# km11.net
KiCad netlist of a schematic drawn in EAGLE
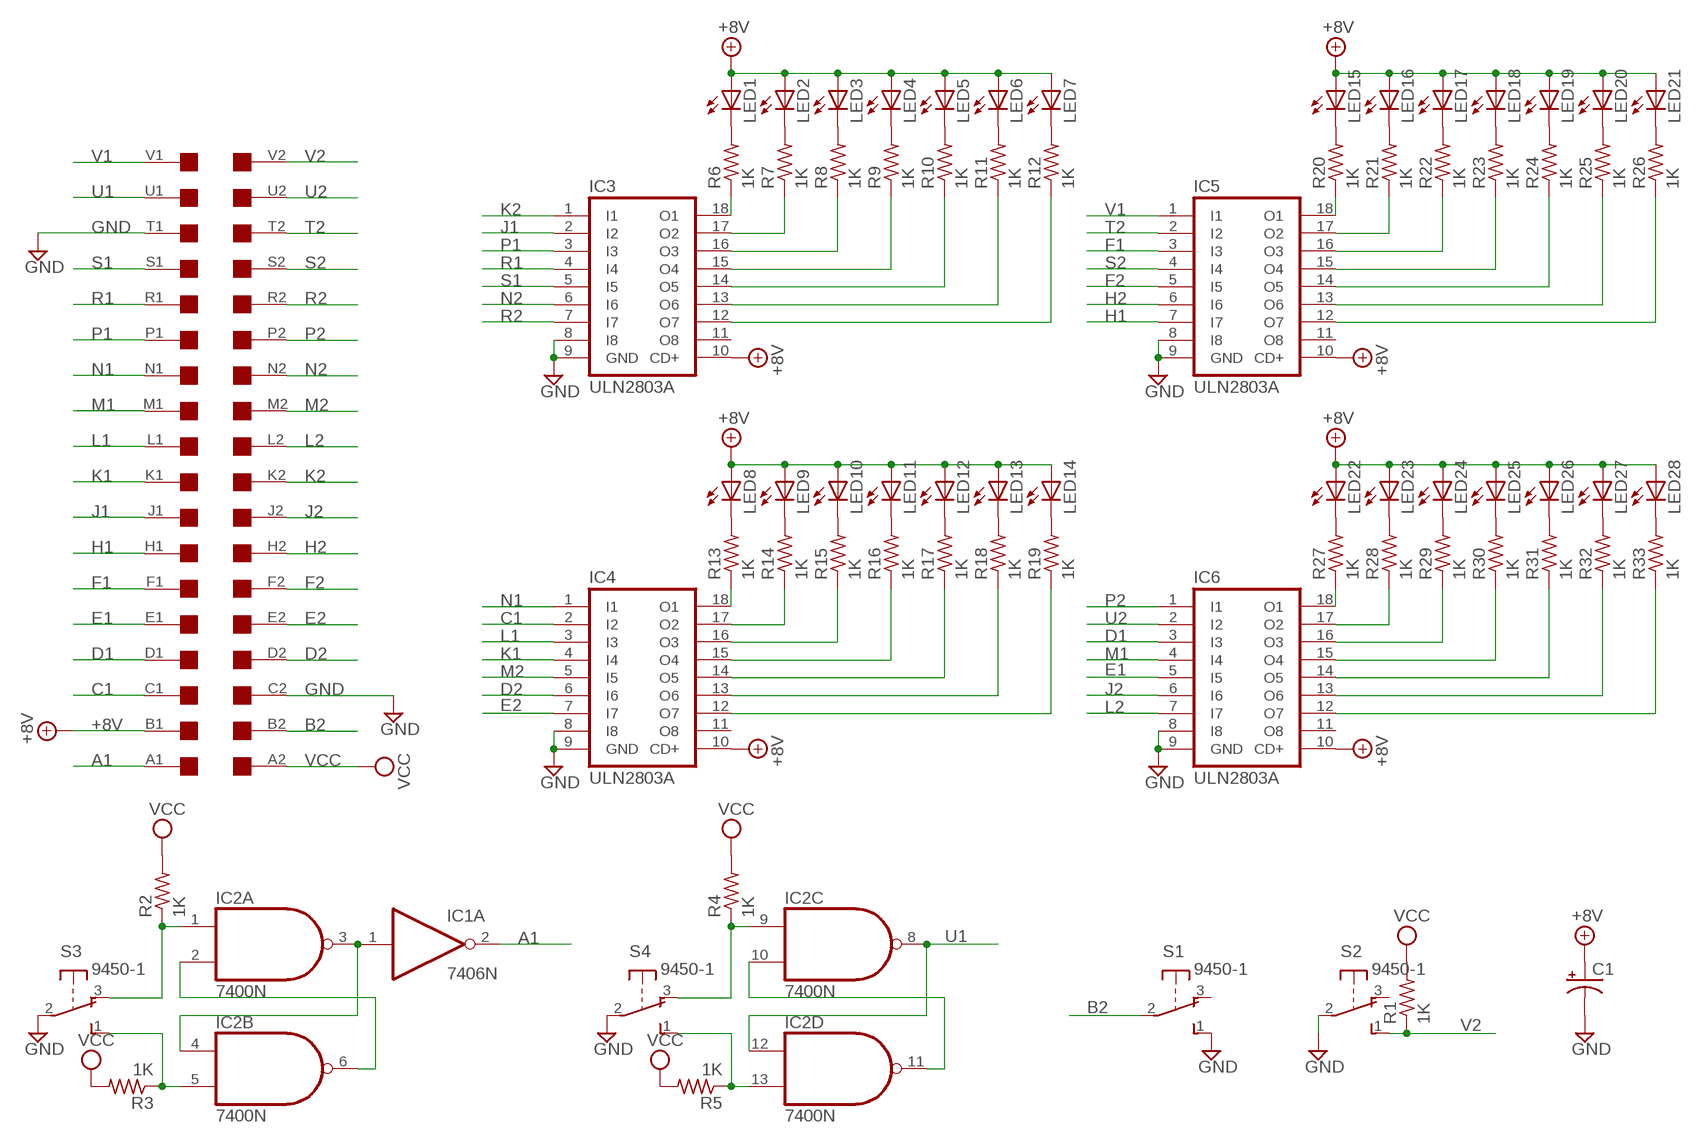
[diagram p0: schematic, sheet 1]

(export (version "E")
  (design (tool "Eeschema 10.0.6"))
  (components
    (comp (ref "C1")
      (value "CPOL-USE22-6AXIAL")
      (footprint "eagle-import:E22-6")
      (libsource (lib "eagle-import") (part "CPOL-USE22-6AXIAL"))
    )
    (comp (ref "IC1")
      (value "7406N")
      (footprint "eagle-import:DIL14")
      (libsource (lib "eagle-import") (part "7406N"))
    )
    (comp (ref "IC2")
      (value "7400N")
      (footprint "eagle-import:DIL14")
      (libsource (lib "eagle-import") (part "7400N"))
    )
    (comp (ref "IC3")
      (value "ULN2803A")
      (footprint "eagle-import:DIL18")
      (libsource (lib "eagle-import") (part "ULN2803A"))
    )
    (comp (ref "IC4")
      (value "ULN2803A")
      (footprint "eagle-import:DIL18")
      (libsource (lib "eagle-import") (part "ULN2803A"))
    )
    (comp (ref "IC5")
      (value "ULN2803A")
      (footprint "eagle-import:DIL18")
      (libsource (lib "eagle-import") (part "ULN2803A"))
    )
    (comp (ref "IC6")
      (value "ULN2803A")
      (footprint "eagle-import:DIL18")
      (libsource (lib "eagle-import") (part "ULN2803A"))
    )
    (comp (ref "LED1")
      (value "LED3MM")
      (footprint "eagle-import:LED3MM")
      (libsource (lib "eagle-import") (part "LED3MM"))
    )
    (comp (ref "LED2")
      (value "LED3MM")
      (footprint "eagle-import:LED3MM")
      (libsource (lib "eagle-import") (part "LED3MM"))
    )
    (comp (ref "LED3")
      (value "LED3MM")
      (footprint "eagle-import:LED3MM")
      (libsource (lib "eagle-import") (part "LED3MM"))
    )
    (comp (ref "LED4")
      (value "LED3MM")
      (footprint "eagle-import:LED3MM")
      (libsource (lib "eagle-import") (part "LED3MM"))
    )
    (comp (ref "LED5")
      (value "LED3MM")
      (footprint "eagle-import:LED3MM")
      (libsource (lib "eagle-import") (part "LED3MM"))
    )
    (comp (ref "LED6")
      (value "LED3MM")
      (footprint "eagle-import:LED3MM")
      (libsource (lib "eagle-import") (part "LED3MM"))
    )
    (comp (ref "LED7")
      (value "LED3MM")
      (footprint "eagle-import:LED3MM")
      (libsource (lib "eagle-import") (part "LED3MM"))
    )
    (comp (ref "LED8")
      (value "LED3MM")
      (footprint "eagle-import:LED3MM")
      (libsource (lib "eagle-import") (part "LED3MM"))
    )
    (comp (ref "LED9")
      (value "LED3MM")
      (footprint "eagle-import:LED3MM")
      (libsource (lib "eagle-import") (part "LED3MM"))
    )
    (comp (ref "LED10")
      (value "LED3MM")
      (footprint "eagle-import:LED3MM")
      (libsource (lib "eagle-import") (part "LED3MM"))
    )
    (comp (ref "LED11")
      (value "LED3MM")
      (footprint "eagle-import:LED3MM")
      (libsource (lib "eagle-import") (part "LED3MM"))
    )
    (comp (ref "LED12")
      (value "LED3MM")
      (footprint "eagle-import:LED3MM")
      (libsource (lib "eagle-import") (part "LED3MM"))
    )
    (comp (ref "LED13")
      (value "LED3MM")
      (footprint "eagle-import:LED3MM")
      (libsource (lib "eagle-import") (part "LED3MM"))
    )
    (comp (ref "LED14")
      (value "LED3MM")
      (footprint "eagle-import:LED3MM")
      (libsource (lib "eagle-import") (part "LED3MM"))
    )
    (comp (ref "LED15")
      (value "LED3MM")
      (footprint "eagle-import:LED3MM")
      (libsource (lib "eagle-import") (part "LED3MM"))
    )
    (comp (ref "LED16")
      (value "LED3MM")
      (footprint "eagle-import:LED3MM")
      (libsource (lib "eagle-import") (part "LED3MM"))
    )
    (comp (ref "LED17")
      (value "LED3MM")
      (footprint "eagle-import:LED3MM")
      (libsource (lib "eagle-import") (part "LED3MM"))
    )
    (comp (ref "LED18")
      (value "LED3MM")
      (footprint "eagle-import:LED3MM")
      (libsource (lib "eagle-import") (part "LED3MM"))
    )
    (comp (ref "LED19")
      (value "LED3MM")
      (footprint "eagle-import:LED3MM")
      (libsource (lib "eagle-import") (part "LED3MM"))
    )
    (comp (ref "LED20")
      (value "LED3MM")
      (footprint "eagle-import:LED3MM")
      (libsource (lib "eagle-import") (part "LED3MM"))
    )
    (comp (ref "LED21")
      (value "LED3MM")
      (footprint "eagle-import:LED3MM")
      (libsource (lib "eagle-import") (part "LED3MM"))
    )
    (comp (ref "LED22")
      (value "LED3MM")
      (footprint "eagle-import:LED3MM")
      (libsource (lib "eagle-import") (part "LED3MM"))
    )
    (comp (ref "LED23")
      (value "LED3MM")
      (footprint "eagle-import:LED3MM")
      (libsource (lib "eagle-import") (part "LED3MM"))
    )
    (comp (ref "LED24")
      (value "LED3MM")
      (footprint "eagle-import:LED3MM")
      (libsource (lib "eagle-import") (part "LED3MM"))
    )
    (comp (ref "LED25")
      (value "LED3MM")
      (footprint "eagle-import:LED3MM")
      (libsource (lib "eagle-import") (part "LED3MM"))
    )
    (comp (ref "LED26")
      (value "LED3MM")
      (footprint "eagle-import:LED3MM")
      (libsource (lib "eagle-import") (part "LED3MM"))
    )
    (comp (ref "LED27")
      (value "LED3MM")
      (footprint "eagle-import:LED3MM")
      (libsource (lib "eagle-import") (part "LED3MM"))
    )
    (comp (ref "LED28")
      (value "LED3MM")
      (footprint "eagle-import:LED3MM")
      (libsource (lib "eagle-import") (part "LED3MM"))
    )
    (comp (ref "R1")
      (value "1K")
      (footprint "eagle-import:0207_10")
      (libsource (lib "eagle-import") (part "R-US_0207/10"))
    )
    (comp (ref "R2")
      (value "1K")
      (footprint "eagle-import:0207_10")
      (libsource (lib "eagle-import") (part "R-US_0207/10"))
    )
    (comp (ref "R3")
      (value "1K")
      (footprint "eagle-import:0207_10")
      (libsource (lib "eagle-import") (part "R-US_0207/10"))
    )
    (comp (ref "R4")
      (value "1K")
      (footprint "eagle-import:0207_10")
      (libsource (lib "eagle-import") (part "R-US_0207/10"))
    )
    (comp (ref "R5")
      (value "1K")
      (footprint "eagle-import:0207_10")
      (libsource (lib "eagle-import") (part "R-US_0207/10"))
    )
    (comp (ref "R6")
      (value "1K")
      (footprint "eagle-import:0207_10")
      (libsource (lib "eagle-import") (part "R-US_0207/10"))
    )
    (comp (ref "R7")
      (value "1K")
      (footprint "eagle-import:0207_10")
      (libsource (lib "eagle-import") (part "R-US_0207/10"))
    )
    (comp (ref "R8")
      (value "1K")
      (footprint "eagle-import:0207_10")
      (libsource (lib "eagle-import") (part "R-US_0207/10"))
    )
    (comp (ref "R9")
      (value "1K")
      (footprint "eagle-import:0207_10")
      (libsource (lib "eagle-import") (part "R-US_0207/10"))
    )
    (comp (ref "R10")
      (value "1K")
      (footprint "eagle-import:0207_10")
      (libsource (lib "eagle-import") (part "R-US_0207/10"))
    )
    (comp (ref "R11")
      (value "1K")
      (footprint "eagle-import:0207_10")
      (libsource (lib "eagle-import") (part "R-US_0207/10"))
    )
    (comp (ref "R12")
      (value "1K")
      (footprint "eagle-import:0207_10")
      (libsource (lib "eagle-import") (part "R-US_0207/10"))
    )
    (comp (ref "R13")
      (value "1K")
      (footprint "eagle-import:0207_10")
      (libsource (lib "eagle-import") (part "R-US_0207/10"))
    )
    (comp (ref "R14")
      (value "1K")
      (footprint "eagle-import:0207_10")
      (libsource (lib "eagle-import") (part "R-US_0207/10"))
    )
    (comp (ref "R15")
      (value "1K")
      (footprint "eagle-import:0207_10")
      (libsource (lib "eagle-import") (part "R-US_0207/10"))
    )
    (comp (ref "R16")
      (value "1K")
      (footprint "eagle-import:0207_10")
      (libsource (lib "eagle-import") (part "R-US_0207/10"))
    )
    (comp (ref "R17")
      (value "1K")
      (footprint "eagle-import:0207_10")
      (libsource (lib "eagle-import") (part "R-US_0207/10"))
    )
    (comp (ref "R18")
      (value "1K")
      (footprint "eagle-import:0207_10")
      (libsource (lib "eagle-import") (part "R-US_0207/10"))
    )
    (comp (ref "R19")
      (value "1K")
      (footprint "eagle-import:0207_10")
      (libsource (lib "eagle-import") (part "R-US_0207/10"))
    )
    (comp (ref "R20")
      (value "1K")
      (footprint "eagle-import:0207_10")
      (libsource (lib "eagle-import") (part "R-US_0207/10"))
    )
    (comp (ref "R21")
      (value "1K")
      (footprint "eagle-import:0207_10")
      (libsource (lib "eagle-import") (part "R-US_0207/10"))
    )
    (comp (ref "R22")
      (value "1K")
      (footprint "eagle-import:0207_10")
      (libsource (lib "eagle-import") (part "R-US_0207/10"))
    )
    (comp (ref "R23")
      (value "1K")
      (footprint "eagle-import:0207_10")
      (libsource (lib "eagle-import") (part "R-US_0207/10"))
    )
    (comp (ref "R24")
      (value "1K")
      (footprint "eagle-import:0207_10")
      (libsource (lib "eagle-import") (part "R-US_0207/10"))
    )
    (comp (ref "R25")
      (value "1K")
      (footprint "eagle-import:0207_10")
      (libsource (lib "eagle-import") (part "R-US_0207/10"))
    )
    (comp (ref "R26")
      (value "1K")
      (footprint "eagle-import:0207_10")
      (libsource (lib "eagle-import") (part "R-US_0207/10"))
    )
    (comp (ref "R27")
      (value "1K")
      (footprint "eagle-import:0207_10")
      (libsource (lib "eagle-import") (part "R-US_0207/10"))
    )
    (comp (ref "R28")
      (value "1K")
      (footprint "eagle-import:0207_10")
      (libsource (lib "eagle-import") (part "R-US_0207/10"))
    )
    (comp (ref "R29")
      (value "1K")
      (footprint "eagle-import:0207_10")
      (libsource (lib "eagle-import") (part "R-US_0207/10"))
    )
    (comp (ref "R30")
      (value "1K")
      (footprint "eagle-import:0207_10")
      (libsource (lib "eagle-import") (part "R-US_0207/10"))
    )
    (comp (ref "R31")
      (value "1K")
      (footprint "eagle-import:0207_10")
      (libsource (lib "eagle-import") (part "R-US_0207/10"))
    )
    (comp (ref "R32")
      (value "1K")
      (footprint "eagle-import:0207_10")
      (libsource (lib "eagle-import") (part "R-US_0207/10"))
    )
    (comp (ref "R33")
      (value "1K")
      (footprint "eagle-import:0207_10")
      (libsource (lib "eagle-import") (part "R-US_0207/10"))
    )
    (comp (ref "S1")
      (value "9450-1")
      (footprint "eagle-import:9450-1")
      (libsource (lib "eagle-import") (part "9450-1"))
    )
    (comp (ref "S2")
      (value "9450-1")
      (footprint "eagle-import:9450-1")
      (libsource (lib "eagle-import") (part "9450-1"))
    )
    (comp (ref "S3")
      (value "9450-1")
      (footprint "eagle-import:9450-1")
      (libsource (lib "eagle-import") (part "9450-1"))
    )
    (comp (ref "S4")
      (value "9450-1")
      (footprint "eagle-import:9450-1")
      (libsource (lib "eagle-import") (part "9450-1"))
    )
    (comp (ref "U$1")
      (value "EDGE-2CONNECTOR")
      (footprint "eagle-import:EDGE-CON2")
      (libsource (lib "eagle-import") (part "EDGE-2CONNECTOR"))
    )
  )
  (nets
    (net (code "1") (name "+8V") (class "Default")
      (node (ref "C1") (pin "+") (pinfunction "+_+") (pintype "passive"))
      (node (ref "IC3") (pin "10") (pinfunction "CD+_10") (pintype "passive"))
      (node (ref "IC4") (pin "10") (pinfunction "CD+_10") (pintype "passive"))
      (node (ref "IC5") (pin "10") (pinfunction "CD+_10") (pintype "passive"))
      (node (ref "IC6") (pin "10") (pinfunction "CD+_10") (pintype "passive"))
      (node (ref "LED1") (pin "A") (pinfunction "A_A") (pintype "passive"))
      (node (ref "LED10") (pin "A") (pinfunction "A_A") (pintype "passive"))
      (node (ref "LED11") (pin "A") (pinfunction "A_A") (pintype "passive"))
      (node (ref "LED12") (pin "A") (pinfunction "A_A") (pintype "passive"))
      (node (ref "LED13") (pin "A") (pinfunction "A_A") (pintype "passive"))
      (node (ref "LED14") (pin "A") (pinfunction "A_A") (pintype "passive"))
      (node (ref "LED15") (pin "A") (pinfunction "A_A") (pintype "passive"))
      (node (ref "LED16") (pin "A") (pinfunction "A_A") (pintype "passive"))
      (node (ref "LED17") (pin "A") (pinfunction "A_A") (pintype "passive"))
      (node (ref "LED18") (pin "A") (pinfunction "A_A") (pintype "passive"))
      (node (ref "LED19") (pin "A") (pinfunction "A_A") (pintype "passive"))
      (node (ref "LED2") (pin "A") (pinfunction "A_A") (pintype "passive"))
      (node (ref "LED20") (pin "A") (pinfunction "A_A") (pintype "passive"))
      (node (ref "LED21") (pin "A") (pinfunction "A_A") (pintype "passive"))
      (node (ref "LED22") (pin "A") (pinfunction "A_A") (pintype "passive"))
      (node (ref "LED23") (pin "A") (pinfunction "A_A") (pintype "passive"))
      (node (ref "LED24") (pin "A") (pinfunction "A_A") (pintype "passive"))
      (node (ref "LED25") (pin "A") (pinfunction "A_A") (pintype "passive"))
      (node (ref "LED26") (pin "A") (pinfunction "A_A") (pintype "passive"))
      (node (ref "LED27") (pin "A") (pinfunction "A_A") (pintype "passive"))
      (node (ref "LED28") (pin "A") (pinfunction "A_A") (pintype "passive"))
      (node (ref "LED3") (pin "A") (pinfunction "A_A") (pintype "passive"))
      (node (ref "LED4") (pin "A") (pinfunction "A_A") (pintype "passive"))
      (node (ref "LED5") (pin "A") (pinfunction "A_A") (pintype "passive"))
      (node (ref "LED6") (pin "A") (pinfunction "A_A") (pintype "passive"))
      (node (ref "LED7") (pin "A") (pinfunction "A_A") (pintype "passive"))
      (node (ref "LED8") (pin "A") (pinfunction "A_A") (pintype "passive"))
      (node (ref "LED9") (pin "A") (pinfunction "A_A") (pintype "passive"))
      (node (ref "U$1") (pin "B1") (pinfunction "1_B1") (pintype "bidirectional"))
    )
    (net (code "2") (name "/A1") (class "Default")
      (node (ref "IC1") (pin "2") (pinfunction "O_2") (pintype "open_collector"))
      (node (ref "U$1") (pin "A1") (pinfunction "1_A1") (pintype "bidirectional"))
    )
    (net (code "3") (name "/B2") (class "Default")
      (node (ref "S1") (pin "2") (pinfunction "P_2") (pintype "passive"))
      (node (ref "U$1") (pin "B2") (pinfunction "1_B2") (pintype "bidirectional"))
    )
    (net (code "4") (name "/C1") (class "Default")
      (node (ref "IC4") (pin "2") (pinfunction "I2_2") (pintype "input"))
      (node (ref "U$1") (pin "C1") (pinfunction "1_C1") (pintype "bidirectional"))
    )
    (net (code "5") (name "/D1") (class "Default")
      (node (ref "IC6") (pin "3") (pinfunction "I3_3") (pintype "input"))
      (node (ref "U$1") (pin "D1") (pinfunction "1_D1") (pintype "bidirectional"))
    )
    (net (code "6") (name "/D2") (class "Default")
      (node (ref "IC4") (pin "6") (pinfunction "I6_6") (pintype "input"))
      (node (ref "U$1") (pin "D2") (pinfunction "1_D2") (pintype "bidirectional"))
    )
    (net (code "7") (name "/E1") (class "Default")
      (node (ref "IC6") (pin "5") (pinfunction "I5_5") (pintype "input"))
      (node (ref "U$1") (pin "E1") (pinfunction "1_E1") (pintype "bidirectional"))
    )
    (net (code "8") (name "/E2") (class "Default")
      (node (ref "IC4") (pin "7") (pinfunction "I7_7") (pintype "input"))
      (node (ref "U$1") (pin "E2") (pinfunction "1_E2") (pintype "bidirectional"))
    )
    (net (code "9") (name "/F1") (class "Default")
      (node (ref "IC5") (pin "3") (pinfunction "I3_3") (pintype "input"))
      (node (ref "U$1") (pin "F1") (pinfunction "1_F1") (pintype "bidirectional"))
    )
    (net (code "10") (name "/F2") (class "Default")
      (node (ref "IC5") (pin "5") (pinfunction "I5_5") (pintype "input"))
      (node (ref "U$1") (pin "F2") (pinfunction "1_F2") (pintype "bidirectional"))
    )
    (net (code "11") (name "/H1") (class "Default")
      (node (ref "IC5") (pin "7") (pinfunction "I7_7") (pintype "input"))
      (node (ref "U$1") (pin "H1") (pinfunction "1_H1") (pintype "bidirectional"))
    )
    (net (code "12") (name "/H2") (class "Default")
      (node (ref "IC5") (pin "6") (pinfunction "I6_6") (pintype "input"))
      (node (ref "U$1") (pin "H2") (pinfunction "1_H2") (pintype "bidirectional"))
    )
    (net (code "13") (name "/J1") (class "Default")
      (node (ref "IC3") (pin "2") (pinfunction "I2_2") (pintype "input"))
      (node (ref "U$1") (pin "J1") (pinfunction "1_J1") (pintype "bidirectional"))
    )
    (net (code "14") (name "/J2") (class "Default")
      (node (ref "IC6") (pin "6") (pinfunction "I6_6") (pintype "input"))
      (node (ref "U$1") (pin "J2") (pinfunction "1_J2") (pintype "bidirectional"))
    )
    (net (code "15") (name "/K1") (class "Default")
      (node (ref "IC4") (pin "4") (pinfunction "I4_4") (pintype "input"))
      (node (ref "U$1") (pin "K1") (pinfunction "1_K1") (pintype "bidirectional"))
    )
    (net (code "16") (name "/K2") (class "Default")
      (node (ref "IC3") (pin "1") (pinfunction "I1_1") (pintype "input"))
      (node (ref "U$1") (pin "K2") (pinfunction "1_K2") (pintype "bidirectional"))
    )
    (net (code "17") (name "/L1") (class "Default")
      (node (ref "IC4") (pin "3") (pinfunction "I3_3") (pintype "input"))
      (node (ref "U$1") (pin "L1") (pinfunction "1_L1") (pintype "bidirectional"))
    )
    (net (code "18") (name "/L2") (class "Default")
      (node (ref "IC6") (pin "7") (pinfunction "I7_7") (pintype "input"))
      (node (ref "U$1") (pin "L2") (pinfunction "1_L2") (pintype "bidirectional"))
    )
    (net (code "19") (name "/M1") (class "Default")
      (node (ref "IC6") (pin "4") (pinfunction "I4_4") (pintype "input"))
      (node (ref "U$1") (pin "M1") (pinfunction "1_M1") (pintype "bidirectional"))
    )
    (net (code "20") (name "/M2") (class "Default")
      (node (ref "IC4") (pin "5") (pinfunction "I5_5") (pintype "input"))
      (node (ref "U$1") (pin "M2") (pinfunction "1_M2") (pintype "bidirectional"))
    )
    (net (code "21") (name "/N1") (class "Default")
      (node (ref "IC4") (pin "1") (pinfunction "I1_1") (pintype "input"))
      (node (ref "U$1") (pin "N1") (pinfunction "1_N1") (pintype "bidirectional"))
    )
    (net (code "22") (name "/N2") (class "Default")
      (node (ref "IC3") (pin "6") (pinfunction "I6_6") (pintype "input"))
      (node (ref "U$1") (pin "N2") (pinfunction "1_N2") (pintype "bidirectional"))
    )
    (net (code "23") (name "/P1") (class "Default")
      (node (ref "IC3") (pin "3") (pinfunction "I3_3") (pintype "input"))
      (node (ref "U$1") (pin "P1") (pinfunction "1_P1") (pintype "bidirectional"))
    )
    (net (code "24") (name "/P2") (class "Default")
      (node (ref "IC6") (pin "1") (pinfunction "I1_1") (pintype "input"))
      (node (ref "U$1") (pin "P2") (pinfunction "1_P2") (pintype "bidirectional"))
    )
    (net (code "25") (name "/R1") (class "Default")
      (node (ref "IC3") (pin "4") (pinfunction "I4_4") (pintype "input"))
      (node (ref "U$1") (pin "R1") (pinfunction "1_R1") (pintype "bidirectional"))
    )
    (net (code "26") (name "/R2") (class "Default")
      (node (ref "IC3") (pin "7") (pinfunction "I7_7") (pintype "input"))
      (node (ref "U$1") (pin "R2") (pinfunction "1_R2") (pintype "bidirectional"))
    )
    (net (code "27") (name "/S1") (class "Default")
      (node (ref "IC3") (pin "5") (pinfunction "I5_5") (pintype "input"))
      (node (ref "U$1") (pin "S1") (pinfunction "1_S1") (pintype "bidirectional"))
    )
    (net (code "28") (name "/S2") (class "Default")
      (node (ref "IC5") (pin "4") (pinfunction "I4_4") (pintype "input"))
      (node (ref "U$1") (pin "S2") (pinfunction "1_S2") (pintype "bidirectional"))
    )
    (net (code "29") (name "/T2") (class "Default")
      (node (ref "IC5") (pin "2") (pinfunction "I2_2") (pintype "input"))
      (node (ref "U$1") (pin "T2") (pinfunction "1_T2") (pintype "bidirectional"))
    )
    (net (code "30") (name "/U1") (class "Default")
      (node (ref "IC2") (pin "12") (pinfunction "I0_12") (pintype "input"))
      (node (ref "IC2") (pin "8") (pinfunction "O_8") (pintype "output"))
      (node (ref "U$1") (pin "U1") (pinfunction "1_U1") (pintype "bidirectional"))
    )
    (net (code "31") (name "/U2") (class "Default")
      (node (ref "IC6") (pin "2") (pinfunction "I2_2") (pintype "input"))
      (node (ref "U$1") (pin "U2") (pinfunction "1_U2") (pintype "bidirectional"))
    )
    (net (code "32") (name "/V1") (class "Default")
      (node (ref "IC5") (pin "1") (pinfunction "I1_1") (pintype "input"))
      (node (ref "U$1") (pin "V1") (pinfunction "1_V1") (pintype "bidirectional"))
    )
    (net (code "33") (name "/V2") (class "Default")
      (node (ref "R1") (pin "1") (pinfunction "1_1") (pintype "passive"))
      (node (ref "S2") (pin "1") (pinfunction "S_1") (pintype "passive"))
      (node (ref "U$1") (pin "V2") (pinfunction "1_V2") (pintype "bidirectional"))
    )
    (net (code "34") (name "GND") (class "Default")
      (node (ref "C1") (pin "-") (pinfunction "-_-") (pintype "passive"))
      (node (ref "IC3") (pin "8") (pinfunction "I8_8") (pintype "input"))
      (node (ref "IC3") (pin "9") (pinfunction "GND_9") (pintype "power_in"))
      (node (ref "IC4") (pin "8") (pinfunction "I8_8") (pintype "input"))
      (node (ref "IC4") (pin "9") (pinfunction "GND_9") (pintype "power_in"))
      (node (ref "IC5") (pin "8") (pinfunction "I8_8") (pintype "input"))
      (node (ref "IC5") (pin "9") (pinfunction "GND_9") (pintype "power_in"))
      (node (ref "IC6") (pin "8") (pinfunction "I8_8") (pintype "input"))
      (node (ref "IC6") (pin "9") (pinfunction "GND_9") (pintype "power_in"))
      (node (ref "S1") (pin "1") (pinfunction "S_1") (pintype "passive"))
      (node (ref "S2") (pin "2") (pinfunction "P_2") (pintype "passive"))
      (node (ref "S3") (pin "2") (pinfunction "P_2") (pintype "passive"))
      (node (ref "S4") (pin "2") (pinfunction "P_2") (pintype "passive"))
      (node (ref "U$1") (pin "C2") (pinfunction "1_C2") (pintype "bidirectional"))
      (node (ref "U$1") (pin "T1") (pinfunction "1_T1") (pintype "bidirectional"))
    )
    (net (code "35") (name "Net-(IC1A-I)") (class "Default")
      (node (ref "IC1") (pin "1") (pinfunction "I_1") (pintype "input"))
      (node (ref "IC2") (pin "3") (pinfunction "O_3") (pintype "output"))
      (node (ref "IC2") (pin "4") (pinfunction "I0_4") (pintype "input"))
    )
    (net (code "36") (name "Net-(IC2A-I0)") (class "Default")
      (node (ref "IC2") (pin "1") (pinfunction "I0_1") (pintype "input"))
      (node (ref "R2") (pin "1") (pinfunction "1_1") (pintype "passive"))
      (node (ref "S3") (pin "3") (pinfunction "O_3") (pintype "passive"))
    )
    (net (code "37") (name "Net-(IC2A-I1)") (class "Default")
      (node (ref "IC2") (pin "2") (pinfunction "I1_2") (pintype "input"))
      (node (ref "IC2") (pin "6") (pinfunction "O_6") (pintype "output"))
    )
    (net (code "38") (name "Net-(IC2B-I1)") (class "Default")
      (node (ref "IC2") (pin "5") (pinfunction "I1_5") (pintype "input"))
      (node (ref "R3") (pin "1") (pinfunction "1_1") (pintype "passive"))
      (node (ref "S3") (pin "1") (pinfunction "S_1") (pintype "passive"))
    )
    (net (code "39") (name "Net-(IC2C-I0)") (class "Default")
      (node (ref "IC2") (pin "9") (pinfunction "I0_9") (pintype "input"))
      (node (ref "R4") (pin "1") (pinfunction "1_1") (pintype "passive"))
      (node (ref "S4") (pin "3") (pinfunction "O_3") (pintype "passive"))
    )
    (net (code "40") (name "Net-(IC2C-I1)") (class "Default")
      (node (ref "IC2") (pin "10") (pinfunction "I1_10") (pintype "input"))
      (node (ref "IC2") (pin "11") (pinfunction "O_11") (pintype "output"))
    )
    (net (code "41") (name "Net-(IC2D-I1)") (class "Default")
      (node (ref "IC2") (pin "13") (pinfunction "I1_13") (pintype "input"))
      (node (ref "R5") (pin "1") (pinfunction "1_1") (pintype "passive"))
      (node (ref "S4") (pin "1") (pinfunction "S_1") (pintype "passive"))
    )
    (net (code "42") (name "Net-(IC3-O1)") (class "Default")
      (node (ref "IC3") (pin "18") (pinfunction "O1_18") (pintype "open_collector"))
      (node (ref "R6") (pin "1") (pinfunction "1_1") (pintype "passive"))
    )
    (net (code "43") (name "Net-(IC3-O2)") (class "Default")
      (node (ref "IC3") (pin "17") (pinfunction "O2_17") (pintype "open_collector"))
      (node (ref "R7") (pin "1") (pinfunction "1_1") (pintype "passive"))
    )
    (net (code "44") (name "Net-(IC3-O3)") (class "Default")
      (node (ref "IC3") (pin "16") (pinfunction "O3_16") (pintype "open_collector"))
      (node (ref "R8") (pin "1") (pinfunction "1_1") (pintype "passive"))
    )
    (net (code "45") (name "Net-(IC3-O4)") (class "Default")
      (node (ref "IC3") (pin "15") (pinfunction "O4_15") (pintype "open_collector"))
      (node (ref "R9") (pin "1") (pinfunction "1_1") (pintype "passive"))
    )
    (net (code "46") (name "Net-(IC3-O5)") (class "Default")
      (node (ref "IC3") (pin "14") (pinfunction "O5_14") (pintype "open_collector"))
      (node (ref "R10") (pin "1") (pinfunction "1_1") (pintype "passive"))
    )
    (net (code "47") (name "Net-(IC3-O6)") (class "Default")
      (node (ref "IC3") (pin "13") (pinfunction "O6_13") (pintype "open_collector"))
      (node (ref "R11") (pin "1") (pinfunction "1_1") (pintype "passive"))
    )
    (net (code "48") (name "Net-(IC3-O7)") (class "Default")
      (node (ref "IC3") (pin "12") (pinfunction "O7_12") (pintype "open_collector"))
      (node (ref "R12") (pin "1") (pinfunction "1_1") (pintype "passive"))
    )
    (net (code "49") (name "Net-(IC4-O1)") (class "Default")
      (node (ref "IC4") (pin "18") (pinfunction "O1_18") (pintype "open_collector"))
      (node (ref "R13") (pin "1") (pinfunction "1_1") (pintype "passive"))
    )
    (net (code "50") (name "Net-(IC4-O2)") (class "Default")
      (node (ref "IC4") (pin "17") (pinfunction "O2_17") (pintype "open_collector"))
      (node (ref "R14") (pin "1") (pinfunction "1_1") (pintype "passive"))
    )
    (net (code "51") (name "Net-(IC4-O3)") (class "Default")
      (node (ref "IC4") (pin "16") (pinfunction "O3_16") (pintype "open_collector"))
      (node (ref "R15") (pin "1") (pinfunction "1_1") (pintype "passive"))
    )
    (net (code "52") (name "Net-(IC4-O4)") (class "Default")
      (node (ref "IC4") (pin "15") (pinfunction "O4_15") (pintype "open_collector"))
      (node (ref "R16") (pin "1") (pinfunction "1_1") (pintype "passive"))
    )
    (net (code "53") (name "Net-(IC4-O5)") (class "Default")
      (node (ref "IC4") (pin "14") (pinfunction "O5_14") (pintype "open_collector"))
      (node (ref "R17") (pin "1") (pinfunction "1_1") (pintype "passive"))
    )
    (net (code "54") (name "Net-(IC4-O6)") (class "Default")
      (node (ref "IC4") (pin "13") (pinfunction "O6_13") (pintype "open_collector"))
      (node (ref "R18") (pin "1") (pinfunction "1_1") (pintype "passive"))
    )
    (net (code "55") (name "Net-(IC4-O7)") (class "Default")
      (node (ref "IC4") (pin "12") (pinfunction "O7_12") (pintype "open_collector"))
      (node (ref "R19") (pin "1") (pinfunction "1_1") (pintype "passive"))
    )
    (net (code "56") (name "Net-(IC5-O1)") (class "Default")
      (node (ref "IC5") (pin "18") (pinfunction "O1_18") (pintype "open_collector"))
      (node (ref "R20") (pin "1") (pinfunction "1_1") (pintype "passive"))
    )
    (net (code "57") (name "Net-(IC5-O2)") (class "Default")
      (node (ref "IC5") (pin "17") (pinfunction "O2_17") (pintype "open_collector"))
      (node (ref "R21") (pin "1") (pinfunction "1_1") (pintype "passive"))
    )
    (net (code "58") (name "Net-(IC5-O3)") (class "Default")
      (node (ref "IC5") (pin "16") (pinfunction "O3_16") (pintype "open_collector"))
      (node (ref "R22") (pin "1") (pinfunction "1_1") (pintype "passive"))
    )
    (net (code "59") (name "Net-(IC5-O4)") (class "Default")
      (node (ref "IC5") (pin "15") (pinfunction "O4_15") (pintype "open_collector"))
      (node (ref "R23") (pin "1") (pinfunction "1_1") (pintype "passive"))
    )
    (net (code "60") (name "Net-(IC5-O5)") (class "Default")
      (node (ref "IC5") (pin "14") (pinfunction "O5_14") (pintype "open_collector"))
      (node (ref "R24") (pin "1") (pinfunction "1_1") (pintype "passive"))
    )
    (net (code "61") (name "Net-(IC5-O6)") (class "Default")
      (node (ref "IC5") (pin "13") (pinfunction "O6_13") (pintype "open_collector"))
      (node (ref "R25") (pin "1") (pinfunction "1_1") (pintype "passive"))
    )
    (net (code "62") (name "Net-(IC5-O7)") (class "Default")
      (node (ref "IC5") (pin "12") (pinfunction "O7_12") (pintype "open_collector"))
      (node (ref "R26") (pin "1") (pinfunction "1_1") (pintype "passive"))
    )
    (net (code "63") (name "Net-(IC6-O1)") (class "Default")
      (node (ref "IC6") (pin "18") (pinfunction "O1_18") (pintype "open_collector"))
      (node (ref "R27") (pin "1") (pinfunction "1_1") (pintype "passive"))
    )
    (net (code "64") (name "Net-(IC6-O2)") (class "Default")
      (node (ref "IC6") (pin "17") (pinfunction "O2_17") (pintype "open_collector"))
      (node (ref "R28") (pin "1") (pinfunction "1_1") (pintype "passive"))
    )
    (net (code "65") (name "Net-(IC6-O3)") (class "Default")
      (node (ref "IC6") (pin "16") (pinfunction "O3_16") (pintype "open_collector"))
      (node (ref "R29") (pin "1") (pinfunction "1_1") (pintype "passive"))
    )
    (net (code "66") (name "Net-(IC6-O4)") (class "Default")
      (node (ref "IC6") (pin "15") (pinfunction "O4_15") (pintype "open_collector"))
      (node (ref "R30") (pin "1") (pinfunction "1_1") (pintype "passive"))
    )
    (net (code "67") (name "Net-(IC6-O5)") (class "Default")
      (node (ref "IC6") (pin "14") (pinfunction "O5_14") (pintype "open_collector"))
      (node (ref "R31") (pin "1") (pinfunction "1_1") (pintype "passive"))
    )
    (net (code "68") (name "Net-(IC6-O6)") (class "Default")
      (node (ref "IC6") (pin "13") (pinfunction "O6_13") (pintype "open_collector"))
      (node (ref "R32") (pin "1") (pinfunction "1_1") (pintype "passive"))
    )
    (net (code "69") (name "Net-(IC6-O7)") (class "Default")
      (node (ref "IC6") (pin "12") (pinfunction "O7_12") (pintype "open_collector"))
      (node (ref "R33") (pin "1") (pinfunction "1_1") (pintype "passive"))
    )
    (net (code "70") (name "Net-(LED1-C)") (class "Default")
      (node (ref "LED1") (pin "K") (pinfunction "C_K") (pintype "passive"))
      (node (ref "R6") (pin "2") (pinfunction "2_2") (pintype "passive"))
    )
    (net (code "71") (name "Net-(LED2-C)") (class "Default")
      (node (ref "LED2") (pin "K") (pinfunction "C_K") (pintype "passive"))
      (node (ref "R7") (pin "2") (pinfunction "2_2") (pintype "passive"))
    )
    (net (code "72") (name "Net-(LED3-C)") (class "Default")
      (node (ref "LED3") (pin "K") (pinfunction "C_K") (pintype "passive"))
      (node (ref "R8") (pin "2") (pinfunction "2_2") (pintype "passive"))
    )
    (net (code "73") (name "Net-(LED4-C)") (class "Default")
      (node (ref "LED4") (pin "K") (pinfunction "C_K") (pintype "passive"))
      (node (ref "R9") (pin "2") (pinfunction "2_2") (pintype "passive"))
    )
    (net (code "74") (name "Net-(LED5-C)") (class "Default")
      (node (ref "LED5") (pin "K") (pinfunction "C_K") (pintype "passive"))
      (node (ref "R10") (pin "2") (pinfunction "2_2") (pintype "passive"))
    )
    (net (code "75") (name "Net-(LED6-C)") (class "Default")
      (node (ref "LED6") (pin "K") (pinfunction "C_K") (pintype "passive"))
      (node (ref "R11") (pin "2") (pinfunction "2_2") (pintype "passive"))
    )
    (net (code "76") (name "Net-(LED7-C)") (class "Default")
      (node (ref "LED7") (pin "K") (pinfunction "C_K") (pintype "passive"))
      (node (ref "R12") (pin "2") (pinfunction "2_2") (pintype "passive"))
    )
    (net (code "77") (name "Net-(LED8-C)") (class "Default")
      (node (ref "LED8") (pin "K") (pinfunction "C_K") (pintype "passive"))
      (node (ref "R13") (pin "2") (pinfunction "2_2") (pintype "passive"))
    )
    (net (code "78") (name "Net-(LED9-C)") (class "Default")
      (node (ref "LED9") (pin "K") (pinfunction "C_K") (pintype "passive"))
      (node (ref "R14") (pin "2") (pinfunction "2_2") (pintype "passive"))
    )
    (net (code "79") (name "Net-(LED10-C)") (class "Default")
      (node (ref "LED10") (pin "K") (pinfunction "C_K") (pintype "passive"))
      (node (ref "R15") (pin "2") (pinfunction "2_2") (pintype "passive"))
    )
    (net (code "80") (name "Net-(LED11-C)") (class "Default")
      (node (ref "LED11") (pin "K") (pinfunction "C_K") (pintype "passive"))
      (node (ref "R16") (pin "2") (pinfunction "2_2") (pintype "passive"))
    )
    (net (code "81") (name "Net-(LED12-C)") (class "Default")
      (node (ref "LED12") (pin "K") (pinfunction "C_K") (pintype "passive"))
      (node (ref "R17") (pin "2") (pinfunction "2_2") (pintype "passive"))
    )
    (net (code "82") (name "Net-(LED13-C)") (class "Default")
      (node (ref "LED13") (pin "K") (pinfunction "C_K") (pintype "passive"))
      (node (ref "R18") (pin "2") (pinfunction "2_2") (pintype "passive"))
    )
    (net (code "83") (name "Net-(LED14-C)") (class "Default")
      (node (ref "LED14") (pin "K") (pinfunction "C_K") (pintype "passive"))
      (node (ref "R19") (pin "2") (pinfunction "2_2") (pintype "passive"))
    )
    (net (code "84") (name "Net-(LED15-C)") (class "Default")
      (node (ref "LED15") (pin "K") (pinfunction "C_K") (pintype "passive"))
      (node (ref "R20") (pin "2") (pinfunction "2_2") (pintype "passive"))
    )
    (net (code "85") (name "Net-(LED16-C)") (class "Default")
      (node (ref "LED16") (pin "K") (pinfunction "C_K") (pintype "passive"))
      (node (ref "R21") (pin "2") (pinfunction "2_2") (pintype "passive"))
    )
    (net (code "86") (name "Net-(LED17-C)") (class "Default")
      (node (ref "LED17") (pin "K") (pinfunction "C_K") (pintype "passive"))
      (node (ref "R22") (pin "2") (pinfunction "2_2") (pintype "passive"))
    )
    (net (code "87") (name "Net-(LED18-C)") (class "Default")
      (node (ref "LED18") (pin "K") (pinfunction "C_K") (pintype "passive"))
      (node (ref "R23") (pin "2") (pinfunction "2_2") (pintype "passive"))
    )
    (net (code "88") (name "Net-(LED19-C)") (class "Default")
      (node (ref "LED19") (pin "K") (pinfunction "C_K") (pintype "passive"))
      (node (ref "R24") (pin "2") (pinfunction "2_2") (pintype "passive"))
    )
    (net (code "89") (name "Net-(LED20-C)") (class "Default")
      (node (ref "LED20") (pin "K") (pinfunction "C_K") (pintype "passive"))
      (node (ref "R25") (pin "2") (pinfunction "2_2") (pintype "passive"))
    )
    (net (code "90") (name "Net-(LED21-C)") (class "Default")
      (node (ref "LED21") (pin "K") (pinfunction "C_K") (pintype "passive"))
      (node (ref "R26") (pin "2") (pinfunction "2_2") (pintype "passive"))
    )
    (net (code "91") (name "Net-(LED22-C)") (class "Default")
      (node (ref "LED22") (pin "K") (pinfunction "C_K") (pintype "passive"))
      (node (ref "R27") (pin "2") (pinfunction "2_2") (pintype "passive"))
    )
    (net (code "92") (name "Net-(LED23-C)") (class "Default")
      (node (ref "LED23") (pin "K") (pinfunction "C_K") (pintype "passive"))
      (node (ref "R28") (pin "2") (pinfunction "2_2") (pintype "passive"))
    )
    (net (code "93") (name "Net-(LED24-C)") (class "Default")
      (node (ref "LED24") (pin "K") (pinfunction "C_K") (pintype "passive"))
      (node (ref "R29") (pin "2") (pinfunction "2_2") (pintype "passive"))
    )
    (net (code "94") (name "Net-(LED25-C)") (class "Default")
      (node (ref "LED25") (pin "K") (pinfunction "C_K") (pintype "passive"))
      (node (ref "R30") (pin "2") (pinfunction "2_2") (pintype "passive"))
    )
    (net (code "95") (name "Net-(LED26-C)") (class "Default")
      (node (ref "LED26") (pin "K") (pinfunction "C_K") (pintype "passive"))
      (node (ref "R31") (pin "2") (pinfunction "2_2") (pintype "passive"))
    )
    (net (code "96") (name "Net-(LED27-C)") (class "Default")
      (node (ref "LED27") (pin "K") (pinfunction "C_K") (pintype "passive"))
      (node (ref "R32") (pin "2") (pinfunction "2_2") (pintype "passive"))
    )
    (net (code "97") (name "Net-(LED28-C)") (class "Default")
      (node (ref "LED28") (pin "K") (pinfunction "C_K") (pintype "passive"))
      (node (ref "R33") (pin "2") (pinfunction "2_2") (pintype "passive"))
    )
    (net (code "98") (name "VCC") (class "Default")
      (node (ref "R1") (pin "2") (pinfunction "2_2") (pintype "passive"))
      (node (ref "R2") (pin "2") (pinfunction "2_2") (pintype "passive"))
      (node (ref "R3") (pin "2") (pinfunction "2_2") (pintype "passive"))
      (node (ref "R4") (pin "2") (pinfunction "2_2") (pintype "passive"))
      (node (ref "R5") (pin "2") (pinfunction "2_2") (pintype "passive"))
      (node (ref "U$1") (pin "A2") (pinfunction "1_A2") (pintype "bidirectional"))
    )
    (net (code "99") (name "unconnected-(IC3-O8-Pad11)") (class "Default")
      (node (ref "IC3") (pin "11") (pinfunction "O8_11") (pintype "open_collector"))
    )
    (net (code "100") (name "unconnected-(IC4-O8-Pad11)") (class "Default")
      (node (ref "IC4") (pin "11") (pinfunction "O8_11") (pintype "open_collector"))
    )
    (net (code "101") (name "unconnected-(IC5-O8-Pad11)") (class "Default")
      (node (ref "IC5") (pin "11") (pinfunction "O8_11") (pintype "open_collector"))
    )
    (net (code "102") (name "unconnected-(IC6-O8-Pad11)") (class "Default")
      (node (ref "IC6") (pin "11") (pinfunction "O8_11") (pintype "open_collector"))
    )
    (net (code "103") (name "unconnected-(S1-O-Pad3)") (class "Default")
      (node (ref "S1") (pin "3") (pinfunction "O_3") (pintype "passive"))
    )
    (net (code "104") (name "unconnected-(S2-O-Pad3)") (class "Default")
      (node (ref "S2") (pin "3") (pinfunction "O_3") (pintype "passive"))
    )
  )
)
